# ScanGen10.net
KiCad netlist of a schematic drawn in EAGLE
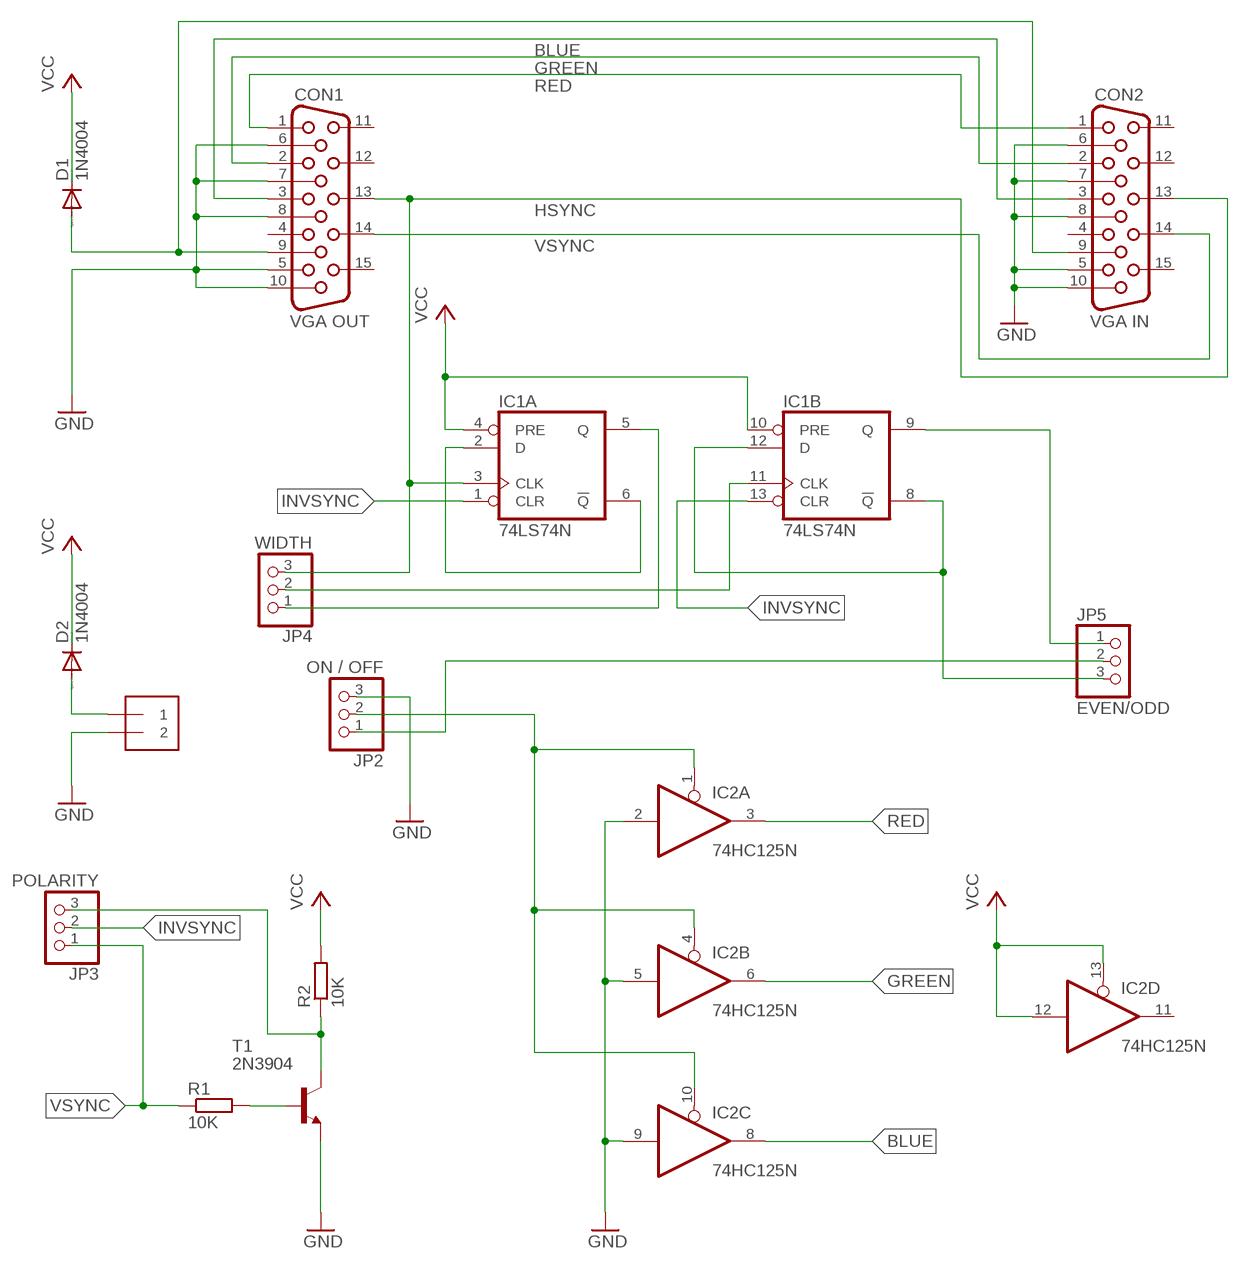
[diagram p0: schematic, sheet 1]

(export (version "E")
  (design (tool "Eeschema 10.0.6"))
  (components
    (comp (ref "CON1")
      (value "VGA OUT")
      (footprint "eagle-import:HDF15H")
      (libsource (lib "eagle-import") (part "HF15H"))
    )
    (comp (ref "CON2")
      (value "VGA IN")
      (footprint "eagle-import:HDF15H")
      (libsource (lib "eagle-import") (part "HF15H"))
    )
    (comp (ref "D1")
      (value "1N4004")
      (footprint "eagle-import:DO41-10")
      (libsource (lib "eagle-import") (part "1N4004"))
    )
    (comp (ref "D2")
      (value "1N4004")
      (footprint "eagle-import:DO41-10")
      (libsource (lib "eagle-import") (part "1N4004"))
    )
    (comp (ref "IC1")
      (value "74LS74N")
      (footprint "eagle-import:DIL14")
      (libsource (lib "eagle-import") (part "7474NLS"))
    )
    (comp (ref "IC2")
      (value "74HC125N")
      (footprint "eagle-import:DIL14")
      (libsource (lib "eagle-import") (part "74125NHC"))
    )
    (comp (ref "JP1")
      (value "+ 5V -")
      (footprint "eagle-import:1X2-3.5MM")
      (libsource (lib "eagle-import") (part "1X2-3.5MM"))
    )
    (comp (ref "JP2")
      (value "ON / OFF")
      (footprint "eagle-import:1X03")
      (libsource (lib "eagle-import") (part "PINHD-1X3"))
    )
    (comp (ref "JP3")
      (value "POLARITY")
      (footprint "eagle-import:1X03")
      (libsource (lib "eagle-import") (part "PINHD-1X3"))
    )
    (comp (ref "JP4")
      (value "WIDTH")
      (footprint "eagle-import:1X03")
      (libsource (lib "eagle-import") (part "PINHD-1X3"))
    )
    (comp (ref "JP5")
      (value "EVEN/ODD")
      (footprint "eagle-import:1X03")
      (libsource (lib "eagle-import") (part "PINHD-1X3"))
    )
    (comp (ref "R1")
      (value "10K")
      (footprint "eagle-import:0204_7")
      (libsource (lib "eagle-import") (part "R-EU_0204/7"))
    )
    (comp (ref "R2")
      (value "10K")
      (footprint "eagle-import:0204_7")
      (libsource (lib "eagle-import") (part "R-EU_0204/7"))
    )
    (comp (ref "T1")
      (value "2N3904")
      (footprint "eagle-import:TO92")
      (libsource (lib "eagle-import") (part "2N3904"))
    )
  )
  (nets
    (net (code "1") (name "/HSYNC") (class "Default")
      (node (ref "CON1") (pin "13") (pinfunction "13_13") (pintype "passive"))
      (node (ref "CON2") (pin "13") (pinfunction "13_13") (pintype "passive"))
      (node (ref "IC1") (pin "3") (pinfunction "CLK_3") (pintype "input"))
      (node (ref "JP4") (pin "3") (pinfunction "3_3") (pintype "passive"))
    )
    (net (code "2") (name "BLUE") (class "Default")
      (node (ref "CON1") (pin "3") (pinfunction "3_3") (pintype "passive"))
      (node (ref "CON2") (pin "3") (pinfunction "3_3") (pintype "passive"))
      (node (ref "IC2") (pin "8") (pinfunction "O_8") (pintype "tri_state"))
    )
    (net (code "3") (name "GND") (class "Default")
      (node (ref "CON1") (pin "10") (pinfunction "10_10") (pintype "passive"))
      (node (ref "CON1") (pin "5") (pinfunction "5_5") (pintype "passive"))
      (node (ref "CON1") (pin "6") (pinfunction "6_6") (pintype "passive"))
      (node (ref "CON1") (pin "7") (pinfunction "7_7") (pintype "passive"))
      (node (ref "CON1") (pin "8") (pinfunction "8_8") (pintype "passive"))
      (node (ref "CON2") (pin "10") (pinfunction "10_10") (pintype "passive"))
      (node (ref "CON2") (pin "5") (pinfunction "5_5") (pintype "passive"))
      (node (ref "CON2") (pin "6") (pinfunction "6_6") (pintype "passive"))
      (node (ref "CON2") (pin "7") (pinfunction "7_7") (pintype "passive"))
      (node (ref "CON2") (pin "8") (pinfunction "8_8") (pintype "passive"))
      (node (ref "IC2") (pin "2") (pinfunction "I_2") (pintype "input"))
      (node (ref "IC2") (pin "5") (pinfunction "I_5") (pintype "input"))
      (node (ref "IC2") (pin "9") (pinfunction "I_9") (pintype "input"))
      (node (ref "JP1") (pin "2") (pinfunction "2_2") (pintype "passive"))
      (node (ref "JP2") (pin "3") (pinfunction "3_3") (pintype "passive"))
      (node (ref "T1") (pin "3") (pinfunction "E_3") (pintype "passive"))
    )
    (net (code "4") (name "GREEN") (class "Default")
      (node (ref "CON1") (pin "2") (pinfunction "2_2") (pintype "passive"))
      (node (ref "CON2") (pin "2") (pinfunction "2_2") (pintype "passive"))
      (node (ref "IC2") (pin "6") (pinfunction "O_6") (pintype "tri_state"))
    )
    (net (code "5") (name "INVSYNC") (class "Default")
      (node (ref "IC1") (pin "1") (pinfunction "CLR_1") (pintype "input"))
      (node (ref "IC1") (pin "13") (pinfunction "CLR_13") (pintype "input"))
      (node (ref "JP3") (pin "2") (pinfunction "2_2") (pintype "passive"))
    )
    (net (code "6") (name "Net-(CON1-Pad9)") (class "Default")
      (node (ref "CON1") (pin "9") (pinfunction "9_9") (pintype "passive"))
      (node (ref "CON2") (pin "9") (pinfunction "9_9") (pintype "passive"))
      (node (ref "D1") (pin "A") (pinfunction "A_A") (pintype "passive"))
    )
    (net (code "7") (name "Net-(D2-PadA)") (class "Default")
      (node (ref "D2") (pin "A") (pinfunction "A_A") (pintype "passive"))
      (node (ref "JP1") (pin "1") (pinfunction "1_1") (pintype "passive"))
    )
    (net (code "8") (name "Net-(IC1A-D)") (class "Default")
      (node (ref "IC1") (pin "2") (pinfunction "D_2") (pintype "input"))
      (node (ref "IC1") (pin "6") (pinfunction "~{Q}_6") (pintype "output"))
    )
    (net (code "9") (name "Net-(IC1A-Q)") (class "Default")
      (node (ref "IC1") (pin "5") (pinfunction "Q_5") (pintype "output"))
      (node (ref "JP4") (pin "1") (pinfunction "1_1") (pintype "passive"))
    )
    (net (code "10") (name "Net-(IC1B-CLK)") (class "Default")
      (node (ref "IC1") (pin "11") (pinfunction "CLK_11") (pintype "input"))
      (node (ref "JP4") (pin "2") (pinfunction "2_2") (pintype "passive"))
    )
    (net (code "11") (name "Net-(IC1B-D)") (class "Default")
      (node (ref "IC1") (pin "12") (pinfunction "D_12") (pintype "input"))
      (node (ref "IC1") (pin "8") (pinfunction "~{Q}_8") (pintype "output"))
      (node (ref "JP5") (pin "3") (pinfunction "3_3") (pintype "passive"))
    )
    (net (code "12") (name "Net-(IC1B-Q)") (class "Default")
      (node (ref "IC1") (pin "9") (pinfunction "Q_9") (pintype "output"))
      (node (ref "JP5") (pin "1") (pinfunction "1_1") (pintype "passive"))
    )
    (net (code "13") (name "Net-(IC2A-OE)") (class "Default")
      (node (ref "IC2") (pin "1") (pinfunction "OE_1") (pintype "input"))
      (node (ref "IC2") (pin "10") (pinfunction "OE_10") (pintype "input"))
      (node (ref "IC2") (pin "4") (pinfunction "OE_4") (pintype "input"))
      (node (ref "JP2") (pin "2") (pinfunction "2_2") (pintype "passive"))
    )
    (net (code "14") (name "Net-(JP2-Pad1)") (class "Default")
      (node (ref "JP2") (pin "1") (pinfunction "1_1") (pintype "passive"))
      (node (ref "JP5") (pin "2") (pinfunction "2_2") (pintype "passive"))
    )
    (net (code "15") (name "Net-(T1-B)") (class "Default")
      (node (ref "R1") (pin "2") (pinfunction "2_2") (pintype "passive"))
      (node (ref "T1") (pin "2") (pinfunction "B_2") (pintype "passive"))
    )
    (net (code "16") (name "Net-(T1-C)") (class "Default")
      (node (ref "JP3") (pin "3") (pinfunction "3_3") (pintype "passive"))
      (node (ref "R2") (pin "1") (pinfunction "1_1") (pintype "passive"))
      (node (ref "T1") (pin "1") (pinfunction "C_1") (pintype "passive"))
    )
    (net (code "17") (name "RED") (class "Default")
      (node (ref "CON1") (pin "1") (pinfunction "1_1") (pintype "passive"))
      (node (ref "CON2") (pin "1") (pinfunction "1_1") (pintype "passive"))
      (node (ref "IC2") (pin "3") (pinfunction "O_3") (pintype "tri_state"))
    )
    (net (code "18") (name "VCC") (class "Default")
      (node (ref "D1") (pin "C") (pinfunction "C_C") (pintype "passive"))
      (node (ref "D2") (pin "C") (pinfunction "C_C") (pintype "passive"))
      (node (ref "IC1") (pin "10") (pinfunction "PRE_10") (pintype "input"))
      (node (ref "IC1") (pin "4") (pinfunction "PRE_4") (pintype "input"))
      (node (ref "IC2") (pin "12") (pinfunction "I_12") (pintype "input"))
      (node (ref "IC2") (pin "13") (pinfunction "OE_13") (pintype "input"))
      (node (ref "R2") (pin "2") (pinfunction "2_2") (pintype "passive"))
    )
    (net (code "19") (name "VSYNC") (class "Default")
      (node (ref "CON1") (pin "14") (pinfunction "14_14") (pintype "passive"))
      (node (ref "CON2") (pin "14") (pinfunction "14_14") (pintype "passive"))
      (node (ref "JP3") (pin "1") (pinfunction "1_1") (pintype "passive"))
      (node (ref "R1") (pin "1") (pinfunction "1_1") (pintype "passive"))
    )
    (net (code "20") (name "unconnected-(CON1-Pad4)") (class "Default")
      (node (ref "CON1") (pin "4") (pinfunction "4_4") (pintype "passive"))
    )
    (net (code "21") (name "unconnected-(CON1-Pad11)") (class "Default")
      (node (ref "CON1") (pin "11") (pinfunction "11_11") (pintype "passive"))
    )
    (net (code "22") (name "unconnected-(CON1-Pad12)") (class "Default")
      (node (ref "CON1") (pin "12") (pinfunction "12_12") (pintype "passive"))
    )
    (net (code "23") (name "unconnected-(CON1-Pad15)") (class "Default")
      (node (ref "CON1") (pin "15") (pinfunction "15_15") (pintype "passive"))
    )
    (net (code "24") (name "unconnected-(CON2-Pad4)") (class "Default")
      (node (ref "CON2") (pin "4") (pinfunction "4_4") (pintype "passive"))
    )
    (net (code "25") (name "unconnected-(CON2-Pad11)") (class "Default")
      (node (ref "CON2") (pin "11") (pinfunction "11_11") (pintype "passive"))
    )
    (net (code "26") (name "unconnected-(CON2-Pad12)") (class "Default")
      (node (ref "CON2") (pin "12") (pinfunction "12_12") (pintype "passive"))
    )
    (net (code "27") (name "unconnected-(CON2-Pad15)") (class "Default")
      (node (ref "CON2") (pin "15") (pinfunction "15_15") (pintype "passive"))
    )
    (net (code "28") (name "unconnected-(IC2D-O-Pad11)") (class "Default")
      (node (ref "IC2") (pin "11") (pinfunction "O_11") (pintype "tri_state"))
    )
  )
)
